# FM_Trap.net
KiCad netlist of a schematic drawn in Altium Designer
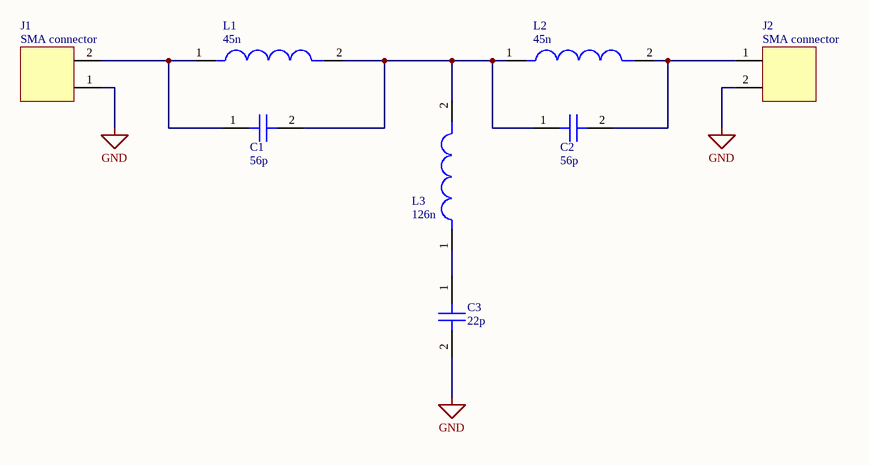
[diagram p0: FM Trap.SchDoc]

(export (version "E")
  (design (tool "Eeschema 10.0.6"))
  (components
    (comp (ref "C1")
      (value "56p")
      (footprint "0603_CAP")
      (libsource (lib "Radolovic_SCH_Library") (part "CAP_0603_generic"))
    )
    (comp (ref "C2")
      (value "56p")
      (footprint "0603_CAP")
      (libsource (lib "Radolovic_SCH_Library") (part "CAP_0603_generic"))
    )
    (comp (ref "C3")
      (value "22p")
      (footprint "0603_CAP")
      (libsource (lib "Radolovic_SCH_Library") (part "CAP_0603_generic"))
    )
    (comp (ref "J1") (value "SMA connector") (libsource (lib "") (part "HEADER_1x2_0.254MM_1")))
    (comp (ref "J2")
      (value "SMA connector")
      (libsource (lib "Radolovic_SCH_Library") (part "HEADER_1x2_0.254MM"))
    )
    (comp (ref "L1")
      (value "45n")
      (footprint "0603_CAP")
      (libsource (lib "Radolovic_SCH_Library") (part "IND_air_0603_generic"))
    )
    (comp (ref "L2")
      (value "45n")
      (footprint "0603_CAP")
      (libsource (lib "Radolovic_SCH_Library") (part "IND_air_0603_generic"))
    )
    (comp (ref "L3")
      (value "126n")
      (footprint "0603_CAP")
      (libsource (lib "Radolovic_SCH_Library") (part "IND_air_0603_generic"))
    )
  )
  (nets
    (net (code "1") (name "GND") (class "Default")
      (node (ref "C3") (pin "2") (pintype "passive"))
      (node (ref "J1") (pin "1") (pintype "passive"))
      (node (ref "J2") (pin "2") (pintype "passive"))
    )
    (net (code "2") (name "Net-(C1-Pad1)") (class "Default")
      (node (ref "C1") (pin "1") (pintype "passive"))
      (node (ref "J1") (pin "2") (pintype "passive"))
      (node (ref "L1") (pin "1") (pintype "passive"))
    )
    (net (code "3") (name "Net-(C1-Pad2)") (class "Default")
      (node (ref "C1") (pin "2") (pintype "passive"))
      (node (ref "C2") (pin "1") (pintype "passive"))
      (node (ref "L1") (pin "2") (pintype "passive"))
      (node (ref "L2") (pin "1") (pintype "passive"))
      (node (ref "L3") (pin "2") (pintype "passive"))
    )
    (net (code "4") (name "Net-(C2-Pad2)") (class "Default")
      (node (ref "C2") (pin "2") (pintype "passive"))
      (node (ref "J2") (pin "1") (pintype "passive"))
      (node (ref "L2") (pin "2") (pintype "passive"))
    )
    (net (code "5") (name "Net-(C3-Pad1)") (class "Default")
      (node (ref "C3") (pin "1") (pintype "passive"))
      (node (ref "L3") (pin "1") (pintype "passive"))
    )
  )
)
